# Backplane.net
KiCad netlist of a schematic drawn in Altium Designer
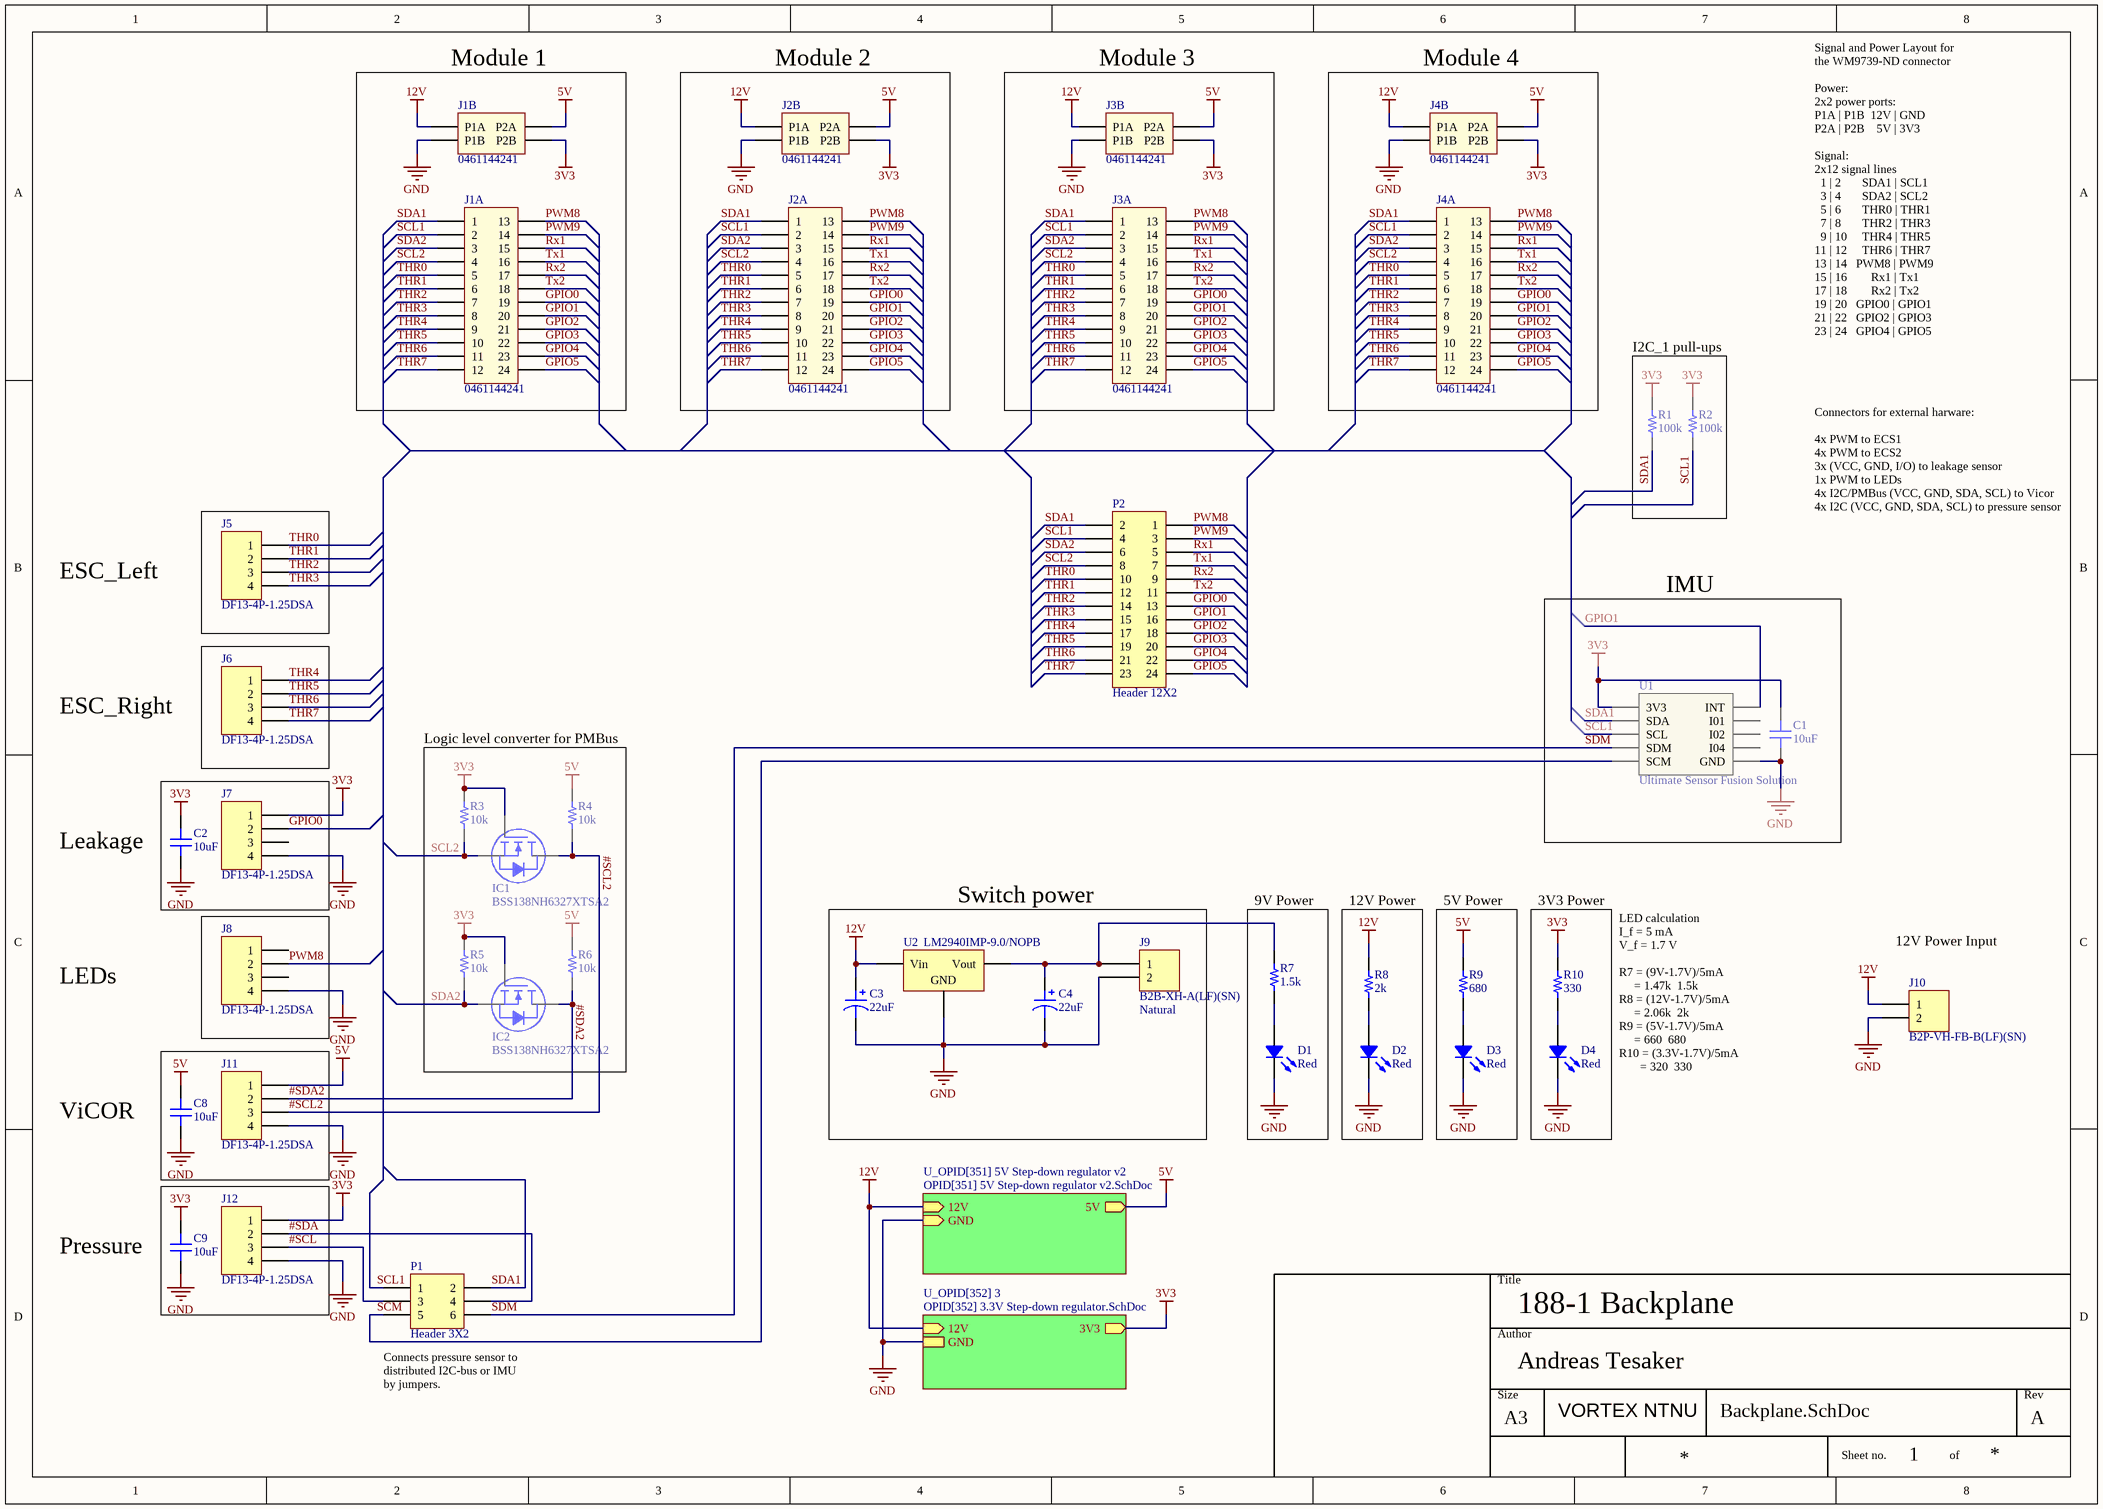
[diagram p0: Backplane.SchDoc]

(export (version "E")
  (design (tool "Eeschema 10.0.6"))
  (components
    (comp (ref "C1")
      (value "10uF")
      (footprint "CAP 1210/3225 - 2.8MM")
      (description "CAP CER 10UF 50V X7S 1210")
      (fields
        (field (name "PART NUMBER") "C3225X7S1H106M250AB")
        (field (name "MANUFACTURER") "TDK Corporation")
      )
      (libsource (lib "Celestial Library Database") (part "Capacitor"))
    )
    (comp (ref "C2")
      (value "10uF")
      (footprint "CAP 1210/3225 - 2.8MM")
      (description "CAP CER 10UF 50V X7S 1210")
      (fields
        (field (name "PART NUMBER") "C3225X7S1H106M250AB")
        (field (name "MANUFACTURER") "TDK Corporation")
      )
      (libsource (lib "Celestial Library Database") (part "Capacitor"))
    )
    (comp (ref "C3")
      (value "22uF")
      (footprint "CAP ALUM 6.6MM")
      (description "CAP ALUM 22UF 20% 35V SMD")
      (fields (field (name "PART NUMBER") "UWJ1V220MCL1GB") (field (name "MANUFACTURER") "Nichicon"))
      (libsource (lib "Celestial Library Database") (part "Polarised Capacitor"))
    )
    (comp (ref "C4")
      (value "22uF")
      (footprint "CAP POL 2917/7343")
      (description "CAP TANT 22UF 20V 20% 2917")
      (fields (field (name "PART NUMBER") "293D226X0020D2TE3") (field (name "MANUFACTURER") "Vishay Sprague"))
      (libsource (lib "Celestial Library Database") (part "Polarised Capacitor"))
    )
    (comp (ref "C8")
      (value "10uF")
      (footprint "CAP 1210/3225 - 2.8MM")
      (description "CAP CER 10UF 50V X7S 1210")
      (fields
        (field (name "PART NUMBER") "C3225X7S1H106M250AB")
        (field (name "MANUFACTURER") "TDK Corporation")
      )
      (libsource (lib "Celestial Library Database") (part "Capacitor"))
    )
    (comp (ref "C9")
      (value "10uF")
      (footprint "CAP 1210/3225 - 2.8MM")
      (description "CAP CER 10UF 50V X7S 1210")
      (fields
        (field (name "PART NUMBER") "C3225X7S1H106M250AB")
        (field (name "MANUFACTURER") "TDK Corporation")
      )
      (libsource (lib "Celestial Library Database") (part "Capacitor"))
    )
    (comp (ref "D1")
      (value "Red")
      (footprint "LED 0805/2012 RED")
      (description "LED RED DIFFUSED 0805 SMD")
      (fields
        (field (name "PART NUMBER") "LH R974-LP-1")
        (field (name "MANUFACTURER") "OSRAM Opto Semiconductors Inc.")
      )
      (libsource (lib "Celestial Library Database") (part "LED"))
    )
    (comp (ref "D2")
      (value "Red")
      (footprint "LED 0805/2012 RED")
      (description "LED RED DIFFUSED 0805 SMD")
      (fields
        (field (name "PART NUMBER") "LH R974-LP-1")
        (field (name "MANUFACTURER") "OSRAM Opto Semiconductors Inc.")
      )
      (libsource (lib "Celestial Library Database") (part "LED"))
    )
    (comp (ref "D3")
      (value "Red")
      (footprint "LED 0805/2012 RED")
      (description "LED RED DIFFUSED 0805 SMD")
      (fields
        (field (name "PART NUMBER") "LH R974-LP-1")
        (field (name "MANUFACTURER") "OSRAM Opto Semiconductors Inc.")
      )
      (libsource (lib "Celestial Library Database") (part "LED"))
    )
    (comp (ref "D4")
      (value "Red")
      (footprint "LED 0805/2012 RED")
      (description "LED RED DIFFUSED 0805 SMD")
      (fields
        (field (name "PART NUMBER") "LH R974-LP-1")
        (field (name "MANUFACTURER") "OSRAM Opto Semiconductors Inc.")
      )
      (libsource (lib "Celestial Library Database") (part "LED"))
    )
    (comp (ref "IC1")
      (value "BSS138NH6327XTSA2")
      (footprint "INFINEON SOT-23-3")
      (description "MOSFET N-CH 60V 230MA SOT-23")
      (fields (field (name "MANUFACTURER") "Infineon Technologies"))
      (libsource (lib "Celestial Library Database") (part "INFINEON MOSFET N-CH SOT-23-3"))
    )
    (comp (ref "IC2")
      (value "BSS138NH6327XTSA2")
      (footprint "INFINEON SOT-23-3")
      (description "MOSFET N-CH 60V 230MA SOT-23")
      (fields (field (name "MANUFACTURER") "Infineon Technologies"))
      (libsource (lib "Celestial Library Database") (part "INFINEON MOSFET N-CH SOT-23-3"))
    )
    (comp (ref "J1")
      (value "0461144241")
      (footprint "LPH_VERT.RECEPT._ASSY_4PX24S")
      (libsource (lib "Vortex-component-database") (part "LPHPower_connector"))
    )
    (comp (ref "J2")
      (value "0461144241")
      (footprint "LPH_VERT.RECEPT._ASSY_4PX24S")
      (libsource (lib "Vortex-component-database") (part "LPHPower_connector"))
    )
    (comp (ref "J3")
      (value "0461144241")
      (footprint "LPH_VERT.RECEPT._ASSY_4PX24S")
      (libsource (lib "Vortex-component-database") (part "LPHPower_connector"))
    )
    (comp (ref "J4")
      (value "0461144241")
      (footprint "LPH_VERT.RECEPT._ASSY_4PX24S")
      (libsource (lib "Vortex-component-database") (part "LPHPower_connector"))
    )
    (comp (ref "J5")
      (value "DF13-4P-1.25DSA")
      (footprint "HDRV4W35P125_1X4_665X340X430P")
      (libsource (lib "Vortex-component-database") (part "Header 4"))
    )
    (comp (ref "J6")
      (value "DF13-4P-1.25DSA")
      (footprint "HDRV4W35P125_1X4_665X340X430P")
      (libsource (lib "Vortex-component-database") (part "Header 4"))
    )
    (comp (ref "J7")
      (value "DF13-4P-1.25DSA")
      (footprint "HDRV4W35P125_1X4_665X340X430P")
      (libsource (lib "Vortex-component-database") (part "Header 4"))
    )
    (comp (ref "J8")
      (value "DF13-4P-1.25DSA")
      (footprint "HDRV4W35P125_1X4_665X340X430P")
      (libsource (lib "Vortex-component-database") (part "Header 4"))
    )
    (comp (ref "J9")
      (value "B2B-XH-A(LF)(SN)")
      (footprint "JST XH B2B-XH-A")
      (description "CONN HEADER XH TOP 2POS 2.5MM")
      (fields (field (name "COLOUR") "Natural") (field (name "MANUFACTURER") "JST Sales America Inc."))
      (libsource (lib "Celestial Library Database") (part "2 Pin"))
    )
    (comp (ref "J10")
      (value "B2P-VH-FB-B(LF)(SN)")
      (footprint "B2P-VH-FB-B")
      (libsource (lib "Vortex-component-database") (part "Header 2"))
    )
    (comp (ref "J11")
      (value "DF13-4P-1.25DSA")
      (footprint "HDRV4W35P125_1X4_665X340X430P")
      (libsource (lib "Vortex-component-database") (part "Header 4"))
    )
    (comp (ref "J12")
      (value "DF13-4P-1.25DSA")
      (footprint "HDRV4W35P125_1X4_665X340X430P")
      (libsource (lib "Vortex-component-database") (part "Header 4"))
    )
    (comp (ref "P1")
      (value "Header 3X2")
      (footprint "HDR2X3")
      (description "Header, 3-Pin, Dual row")
      (fields (field (name "PUBLISHER") "Altium Limited"))
      (libsource (lib "Miscellaneous Connectors") (part "Header 3X2"))
    )
    (comp (ref "P2")
      (value "Header 12X2")
      (footprint "HDR2X12")
      (description "Header, 12-Pin, Dual row")
      (fields (field (name "PUBLISHER") "Altium Limited"))
      (libsource (lib "Miscellaneous Connectors") (part "Header 12X2"))
    )
    (comp (ref "R1")
      (value "100k")
      (footprint "RES 0805/2012")
      (description "RES SMD 100K OHM 1% 1/8W 0805")
      (fields
        (field (name "PART NUMBER") "ERJ-6ENF1003V")
        (field (name "MANUFACTURER") "Panasonic Electronic Components")
      )
      (libsource (lib "Celestial Library Database") (part "Resistor"))
    )
    (comp (ref "R2")
      (value "100k")
      (footprint "RES 0805/2012")
      (description "RES SMD 100K OHM 1% 1/8W 0805")
      (fields
        (field (name "PART NUMBER") "ERJ-6ENF1003V")
        (field (name "MANUFACTURER") "Panasonic Electronic Components")
      )
      (libsource (lib "Celestial Library Database") (part "Resistor"))
    )
    (comp (ref "R3")
      (value "10k")
      (footprint "RES 0805/2012")
      (description "RES SMD 10K OHM 1% 1/8W 0805")
      (fields
        (field (name "PART NUMBER") "ERJ-6ENF1002V")
        (field (name "MANUFACTURER") "Panasonic Electronic Components")
      )
      (libsource (lib "Celestial Library Database") (part "Resistor"))
    )
    (comp (ref "R4")
      (value "10k")
      (footprint "RES 0805/2012")
      (description "RES SMD 10K OHM 1% 1/8W 0805")
      (fields
        (field (name "PART NUMBER") "ERJ-6ENF1002V")
        (field (name "MANUFACTURER") "Panasonic Electronic Components")
      )
      (libsource (lib "Celestial Library Database") (part "Resistor"))
    )
    (comp (ref "R5")
      (value "10k")
      (footprint "RES 0805/2012")
      (description "RES SMD 10K OHM 1% 1/8W 0805")
      (fields
        (field (name "PART NUMBER") "ERJ-6ENF1002V")
        (field (name "MANUFACTURER") "Panasonic Electronic Components")
      )
      (libsource (lib "Celestial Library Database") (part "Resistor"))
    )
    (comp (ref "R6")
      (value "10k")
      (footprint "RES 0805/2012")
      (description "RES SMD 10K OHM 1% 1/8W 0805")
      (fields
        (field (name "PART NUMBER") "ERJ-6ENF1002V")
        (field (name "MANUFACTURER") "Panasonic Electronic Components")
      )
      (libsource (lib "Celestial Library Database") (part "Resistor"))
    )
    (comp (ref "R7")
      (value "1.5k")
      (footprint "RES 0805/2012")
      (description "RES SMD 1.5K OHM 0.1% 1/8W 0805")
      (fields
        (field (name "PART NUMBER") "ERA-6AEB152V")
        (field (name "MANUFACTURER") "Panasonic Electronic Components")
      )
      (libsource (lib "Celestial Library Database") (part "Resistor"))
    )
    (comp (ref "R8")
      (value "2k")
      (footprint "RES 0805/2012")
      (description "RES SMD 2K OHM 0.1% 1/8W 0805")
      (fields
        (field (name "PART NUMBER") "ERA-6AEB202V")
        (field (name "MANUFACTURER") "Panasonic Electronic Components")
      )
      (libsource (lib "Celestial Library Database") (part "Resistor"))
    )
    (comp (ref "R9")
      (value "680")
      (footprint "RES 0805/2012")
      (description "RES SMD 680 OHM 1% 1/8W 0805")
      (fields
        (field (name "PART NUMBER") "ERJ-6ENF6800V")
        (field (name "MANUFACTURER") "Panasonic Electronic Components")
      )
      (libsource (lib "Celestial Library Database") (part "Resistor"))
    )
    (comp (ref "R10")
      (value "330")
      (footprint "RES 0805/2012")
      (description "RES SMD 330 OHM 5% 1/2W 0805")
      (fields
        (field (name "PART NUMBER") "ERJ-P06J331V")
        (field (name "MANUFACTURER") "Panasonic Electronic Components")
      )
      (libsource (lib "Celestial Library Database") (part "Resistor"))
    )
    (comp (ref "U1")
      (value "Ultimate Sensor Fusion Solution")
      (footprint "Ultimate Sensor Fusion Solution")
      (libsource (lib "Vortex-component-database") (part "Ultimate Sensor Fusion Solution"))
    )
    (comp (ref "U2")
      (value "LM2940IMP-9.0/NOPB")
      (footprint "SOT230P700X180-4N")
      (libsource (lib "Vortex-component-database") (part "Volt_Reg"))
    )
  )
  (nets
    (net (code "1") (name "/GPIO0") (class "Default")
      (node (ref "J1") (pin "19") (pinfunction "19_19") (pintype "passive"))
      (node (ref "J2") (pin "19") (pinfunction "19_19") (pintype "passive"))
      (node (ref "J3") (pin "19") (pinfunction "19_19") (pintype "passive"))
      (node (ref "J4") (pin "19") (pinfunction "19_19") (pintype "passive"))
      (node (ref "J7") (pin "2") (pinfunction "2_2") (pintype "passive"))
      (node (ref "P2") (pin "13") (pinfunction "13_13") (pintype "passive"))
    )
    (net (code "2") (name "/GPIO1") (class "Default")
      (node (ref "J1") (pin "20") (pinfunction "20_20") (pintype "passive"))
      (node (ref "J2") (pin "20") (pinfunction "20_20") (pintype "passive"))
      (node (ref "J3") (pin "20") (pinfunction "20_20") (pintype "passive"))
      (node (ref "J4") (pin "20") (pinfunction "20_20") (pintype "passive"))
      (node (ref "P2") (pin "16") (pinfunction "16_16") (pintype "passive"))
      (node (ref "U1") (pin "6") (pinfunction "INT_6") (pintype "passive"))
    )
    (net (code "3") (name "/GPIO2") (class "Default")
      (node (ref "J1") (pin "21") (pinfunction "21_21") (pintype "passive"))
      (node (ref "J2") (pin "21") (pinfunction "21_21") (pintype "passive"))
      (node (ref "J3") (pin "21") (pinfunction "21_21") (pintype "passive"))
      (node (ref "J4") (pin "21") (pinfunction "21_21") (pintype "passive"))
      (node (ref "P2") (pin "18") (pinfunction "18_18") (pintype "passive"))
    )
    (net (code "4") (name "/GPIO3") (class "Default")
      (node (ref "J1") (pin "22") (pinfunction "22_22") (pintype "passive"))
      (node (ref "J2") (pin "22") (pinfunction "22_22") (pintype "passive"))
      (node (ref "J3") (pin "22") (pinfunction "22_22") (pintype "passive"))
      (node (ref "J4") (pin "22") (pinfunction "22_22") (pintype "passive"))
      (node (ref "P2") (pin "20") (pinfunction "20_20") (pintype "passive"))
    )
    (net (code "5") (name "/GPIO4") (class "Default")
      (node (ref "J1") (pin "23") (pinfunction "23_23") (pintype "passive"))
      (node (ref "J2") (pin "23") (pinfunction "23_23") (pintype "passive"))
      (node (ref "J3") (pin "23") (pinfunction "23_23") (pintype "passive"))
      (node (ref "J4") (pin "23") (pinfunction "23_23") (pintype "passive"))
      (node (ref "P2") (pin "22") (pinfunction "22_22") (pintype "passive"))
    )
    (net (code "6") (name "/GPIO5") (class "Default")
      (node (ref "J1") (pin "24") (pinfunction "24_24") (pintype "passive"))
      (node (ref "J2") (pin "24") (pinfunction "24_24") (pintype "passive"))
      (node (ref "J3") (pin "24") (pinfunction "24_24") (pintype "passive"))
      (node (ref "J4") (pin "24") (pinfunction "24_24") (pintype "passive"))
      (node (ref "P2") (pin "24") (pinfunction "24_24") (pintype "passive"))
    )
    (net (code "7") (name "/PWM8") (class "Default")
      (node (ref "J1") (pin "13") (pinfunction "13_13") (pintype "passive"))
      (node (ref "J2") (pin "13") (pinfunction "13_13") (pintype "passive"))
      (node (ref "J3") (pin "13") (pinfunction "13_13") (pintype "passive"))
      (node (ref "J4") (pin "13") (pinfunction "13_13") (pintype "passive"))
      (node (ref "J8") (pin "2") (pinfunction "2_2") (pintype "passive"))
      (node (ref "P2") (pin "1") (pinfunction "1_1") (pintype "passive"))
    )
    (net (code "8") (name "/PWM9") (class "Default")
      (node (ref "J1") (pin "14") (pinfunction "14_14") (pintype "passive"))
      (node (ref "J2") (pin "14") (pinfunction "14_14") (pintype "passive"))
      (node (ref "J3") (pin "14") (pinfunction "14_14") (pintype "passive"))
      (node (ref "J4") (pin "14") (pinfunction "14_14") (pintype "passive"))
      (node (ref "P2") (pin "3") (pinfunction "3_3") (pintype "passive"))
    )
    (net (code "9") (name "/Rx1") (class "Default")
      (node (ref "J1") (pin "15") (pinfunction "15_15") (pintype "passive"))
      (node (ref "J2") (pin "15") (pinfunction "15_15") (pintype "passive"))
      (node (ref "J3") (pin "15") (pinfunction "15_15") (pintype "passive"))
      (node (ref "J4") (pin "15") (pinfunction "15_15") (pintype "passive"))
      (node (ref "P2") (pin "5") (pinfunction "5_5") (pintype "passive"))
    )
    (net (code "10") (name "/Rx2") (class "Default")
      (node (ref "J1") (pin "17") (pinfunction "17_17") (pintype "passive"))
      (node (ref "J2") (pin "17") (pinfunction "17_17") (pintype "passive"))
      (node (ref "J3") (pin "17") (pinfunction "17_17") (pintype "passive"))
      (node (ref "J4") (pin "17") (pinfunction "17_17") (pintype "passive"))
      (node (ref "P2") (pin "9") (pinfunction "9_9") (pintype "passive"))
    )
    (net (code "11") (name "/SCL1") (class "Default")
      (node (ref "J1") (pin "2") (pinfunction "2_2") (pintype "passive"))
      (node (ref "J2") (pin "2") (pinfunction "2_2") (pintype "passive"))
      (node (ref "J3") (pin "2") (pinfunction "2_2") (pintype "passive"))
      (node (ref "J4") (pin "2") (pinfunction "2_2") (pintype "passive"))
      (node (ref "P1") (pin "1") (pinfunction "1_1") (pintype "passive"))
      (node (ref "P2") (pin "4") (pinfunction "4_4") (pintype "passive"))
      (node (ref "R2") (pin "1") (pinfunction "1_1") (pintype "passive"))
      (node (ref "U1") (pin "4") (pinfunction "SCL_4") (pintype "passive"))
    )
    (net (code "12") (name "/SCL2") (class "Default")
      (node (ref "IC1") (pin "3") (pinfunction "S_3") (pintype "passive"))
      (node (ref "J1") (pin "4") (pinfunction "4_4") (pintype "passive"))
      (node (ref "J2") (pin "4") (pinfunction "4_4") (pintype "passive"))
      (node (ref "J3") (pin "4") (pinfunction "4_4") (pintype "passive"))
      (node (ref "J4") (pin "4") (pinfunction "4_4") (pintype "passive"))
      (node (ref "P2") (pin "8") (pinfunction "8_8") (pintype "passive"))
      (node (ref "R3") (pin "2") (pinfunction "2_2") (pintype "passive"))
    )
    (net (code "13") (name "/SDA1") (class "Default")
      (node (ref "J1") (pin "1") (pinfunction "1_1") (pintype "passive"))
      (node (ref "J2") (pin "1") (pinfunction "1_1") (pintype "passive"))
      (node (ref "J3") (pin "1") (pinfunction "1_1") (pintype "passive"))
      (node (ref "J4") (pin "1") (pinfunction "1_1") (pintype "passive"))
      (node (ref "P1") (pin "2") (pinfunction "2_2") (pintype "passive"))
      (node (ref "P2") (pin "2") (pinfunction "2_2") (pintype "passive"))
      (node (ref "R1") (pin "1") (pinfunction "1_1") (pintype "passive"))
      (node (ref "U1") (pin "5") (pinfunction "SDA_5") (pintype "passive"))
    )
    (net (code "14") (name "/SDA2") (class "Default")
      (node (ref "IC2") (pin "3") (pinfunction "S_3") (pintype "passive"))
      (node (ref "J1") (pin "3") (pinfunction "3_3") (pintype "passive"))
      (node (ref "J2") (pin "3") (pinfunction "3_3") (pintype "passive"))
      (node (ref "J3") (pin "3") (pinfunction "3_3") (pintype "passive"))
      (node (ref "J4") (pin "3") (pinfunction "3_3") (pintype "passive"))
      (node (ref "P2") (pin "6") (pinfunction "6_6") (pintype "passive"))
      (node (ref "R5") (pin "2") (pinfunction "2_2") (pintype "passive"))
    )
    (net (code "15") (name "/THR0") (class "Default")
      (node (ref "J1") (pin "5") (pinfunction "5_5") (pintype "passive"))
      (node (ref "J2") (pin "5") (pinfunction "5_5") (pintype "passive"))
      (node (ref "J3") (pin "5") (pinfunction "5_5") (pintype "passive"))
      (node (ref "J4") (pin "5") (pinfunction "5_5") (pintype "passive"))
      (node (ref "J5") (pin "1") (pinfunction "1_1") (pintype "passive"))
      (node (ref "P2") (pin "10") (pinfunction "10_10") (pintype "passive"))
    )
    (net (code "16") (name "/THR1") (class "Default")
      (node (ref "J1") (pin "6") (pinfunction "6_6") (pintype "passive"))
      (node (ref "J2") (pin "6") (pinfunction "6_6") (pintype "passive"))
      (node (ref "J3") (pin "6") (pinfunction "6_6") (pintype "passive"))
      (node (ref "J4") (pin "6") (pinfunction "6_6") (pintype "passive"))
      (node (ref "J5") (pin "2") (pinfunction "2_2") (pintype "passive"))
      (node (ref "P2") (pin "12") (pinfunction "12_12") (pintype "passive"))
    )
    (net (code "17") (name "/THR2") (class "Default")
      (node (ref "J1") (pin "7") (pinfunction "7_7") (pintype "passive"))
      (node (ref "J2") (pin "7") (pinfunction "7_7") (pintype "passive"))
      (node (ref "J3") (pin "7") (pinfunction "7_7") (pintype "passive"))
      (node (ref "J4") (pin "7") (pinfunction "7_7") (pintype "passive"))
      (node (ref "J5") (pin "3") (pinfunction "3_3") (pintype "passive"))
      (node (ref "P2") (pin "14") (pinfunction "14_14") (pintype "passive"))
    )
    (net (code "18") (name "/THR3") (class "Default")
      (node (ref "J1") (pin "8") (pinfunction "8_8") (pintype "passive"))
      (node (ref "J2") (pin "8") (pinfunction "8_8") (pintype "passive"))
      (node (ref "J3") (pin "8") (pinfunction "8_8") (pintype "passive"))
      (node (ref "J4") (pin "8") (pinfunction "8_8") (pintype "passive"))
      (node (ref "J5") (pin "4") (pinfunction "4_4") (pintype "passive"))
      (node (ref "P2") (pin "15") (pinfunction "15_15") (pintype "passive"))
    )
    (net (code "19") (name "/THR4") (class "Default")
      (node (ref "J1") (pin "9") (pinfunction "9_9") (pintype "passive"))
      (node (ref "J2") (pin "9") (pinfunction "9_9") (pintype "passive"))
      (node (ref "J3") (pin "9") (pinfunction "9_9") (pintype "passive"))
      (node (ref "J4") (pin "9") (pinfunction "9_9") (pintype "passive"))
      (node (ref "J6") (pin "1") (pinfunction "1_1") (pintype "passive"))
      (node (ref "P2") (pin "17") (pinfunction "17_17") (pintype "passive"))
    )
    (net (code "20") (name "/THR5") (class "Default")
      (node (ref "J1") (pin "10") (pinfunction "10_10") (pintype "passive"))
      (node (ref "J2") (pin "10") (pinfunction "10_10") (pintype "passive"))
      (node (ref "J3") (pin "10") (pinfunction "10_10") (pintype "passive"))
      (node (ref "J4") (pin "10") (pinfunction "10_10") (pintype "passive"))
      (node (ref "J6") (pin "2") (pinfunction "2_2") (pintype "passive"))
      (node (ref "P2") (pin "19") (pinfunction "19_19") (pintype "passive"))
    )
    (net (code "21") (name "/THR6") (class "Default")
      (node (ref "J1") (pin "11") (pinfunction "11_11") (pintype "passive"))
      (node (ref "J2") (pin "11") (pinfunction "11_11") (pintype "passive"))
      (node (ref "J3") (pin "11") (pinfunction "11_11") (pintype "passive"))
      (node (ref "J4") (pin "11") (pinfunction "11_11") (pintype "passive"))
      (node (ref "J6") (pin "3") (pinfunction "3_3") (pintype "passive"))
      (node (ref "P2") (pin "21") (pinfunction "21_21") (pintype "passive"))
    )
    (net (code "22") (name "/THR7") (class "Default")
      (node (ref "J1") (pin "12") (pinfunction "12_12") (pintype "passive"))
      (node (ref "J2") (pin "12") (pinfunction "12_12") (pintype "passive"))
      (node (ref "J3") (pin "12") (pinfunction "12_12") (pintype "passive"))
      (node (ref "J4") (pin "12") (pinfunction "12_12") (pintype "passive"))
      (node (ref "J6") (pin "4") (pinfunction "4_4") (pintype "passive"))
      (node (ref "P2") (pin "23") (pinfunction "23_23") (pintype "passive"))
    )
    (net (code "23") (name "/Tx1") (class "Default")
      (node (ref "J1") (pin "16") (pinfunction "16_16") (pintype "passive"))
      (node (ref "J2") (pin "16") (pinfunction "16_16") (pintype "passive"))
      (node (ref "J3") (pin "16") (pinfunction "16_16") (pintype "passive"))
      (node (ref "J4") (pin "16") (pinfunction "16_16") (pintype "passive"))
      (node (ref "P2") (pin "7") (pinfunction "7_7") (pintype "passive"))
    )
    (net (code "24") (name "/Tx2") (class "Default")
      (node (ref "J1") (pin "18") (pinfunction "18_18") (pintype "passive"))
      (node (ref "J2") (pin "18") (pinfunction "18_18") (pintype "passive"))
      (node (ref "J3") (pin "18") (pinfunction "18_18") (pintype "passive"))
      (node (ref "J4") (pin "18") (pinfunction "18_18") (pintype "passive"))
      (node (ref "P2") (pin "11") (pinfunction "11_11") (pintype "passive"))
    )
    (net (code "25") (name "3V3") (class "Default")
      (node (ref "C1") (pin "2") (pinfunction "2_2") (pintype "passive"))
      (node (ref "C2") (pin "2") (pinfunction "2_2") (pintype "passive"))
      (node (ref "C9") (pin "2") (pinfunction "2_2") (pintype "passive"))
      (node (ref "IC1") (pin "1") (pinfunction "G_1") (pintype "passive"))
      (node (ref "IC2") (pin "1") (pinfunction "G_1") (pintype "passive"))
      (node (ref "J1") (pin "P2B") (pinfunction "P2B_P2B") (pintype "passive"))
      (node (ref "J12") (pin "1") (pinfunction "1_1") (pintype "passive"))
      (node (ref "J2") (pin "P2B") (pinfunction "P2B_P2B") (pintype "passive"))
      (node (ref "J3") (pin "P2B") (pinfunction "P2B_P2B") (pintype "passive"))
      (node (ref "J4") (pin "P2B") (pinfunction "P2B_P2B") (pintype "passive"))
      (node (ref "J7") (pin "1") (pinfunction "1_1") (pintype "passive"))
      (node (ref "R1") (pin "2") (pinfunction "2_2") (pintype "passive"))
      (node (ref "R10") (pin "2") (pinfunction "2_2") (pintype "passive"))
      (node (ref "R2") (pin "2") (pinfunction "2_2") (pintype "passive"))
      (node (ref "R3") (pin "1") (pinfunction "1_1") (pintype "passive"))
      (node (ref "R5") (pin "1") (pinfunction "1_1") (pintype "passive"))
      (node (ref "U1") (pin "2") (pinfunction "3V3_2") (pintype "passive"))
    )
    (net (code "26") (name "5V") (class "Default")
      (node (ref "C8") (pin "2") (pinfunction "2_2") (pintype "passive"))
      (node (ref "J1") (pin "P2A") (pinfunction "P2A_P2A") (pintype "passive"))
      (node (ref "J11") (pin "1") (pinfunction "1_1") (pintype "passive"))
      (node (ref "J2") (pin "P2A") (pinfunction "P2A_P2A") (pintype "passive"))
      (node (ref "J3") (pin "P2A") (pinfunction "P2A_P2A") (pintype "passive"))
      (node (ref "J4") (pin "P2A") (pinfunction "P2A_P2A") (pintype "passive"))
      (node (ref "R4") (pin "1") (pinfunction "1_1") (pintype "passive"))
      (node (ref "R6") (pin "1") (pinfunction "1_1") (pintype "passive"))
      (node (ref "R9") (pin "2") (pinfunction "2_2") (pintype "passive"))
    )
    (net (code "27") (name "12V") (class "Default")
      (node (ref "C3") (pin "1") (pinfunction "1_1") (pintype "passive"))
      (node (ref "J1") (pin "P1A") (pinfunction "P1A_P1A") (pintype "passive"))
      (node (ref "J10") (pin "1") (pinfunction "1_1") (pintype "passive"))
      (node (ref "J2") (pin "P1A") (pinfunction "P1A_P1A") (pintype "passive"))
      (node (ref "J3") (pin "P1A") (pinfunction "P1A_P1A") (pintype "passive"))
      (node (ref "J4") (pin "P1A") (pinfunction "P1A_P1A") (pintype "passive"))
      (node (ref "R8") (pin "2") (pinfunction "2_2") (pintype "passive"))
      (node (ref "U2") (pin "1") (pinfunction "Vin_1") (pintype "passive"))
    )
    (net (code "28") (name "GND") (class "Default")
      (node (ref "C1") (pin "1") (pinfunction "1_1") (pintype "passive"))
      (node (ref "C2") (pin "1") (pinfunction "1_1") (pintype "passive"))
      (node (ref "C3") (pin "2") (pinfunction "2_2") (pintype "passive"))
      (node (ref "C4") (pin "2") (pinfunction "2_2") (pintype "passive"))
      (node (ref "C8") (pin "1") (pinfunction "1_1") (pintype "passive"))
      (node (ref "C9") (pin "1") (pinfunction "1_1") (pintype "passive"))
      (node (ref "D1") (pin "2") (pinfunction "2_2") (pintype "passive"))
      (node (ref "D2") (pin "2") (pinfunction "2_2") (pintype "passive"))
      (node (ref "D3") (pin "2") (pinfunction "2_2") (pintype "passive"))
      (node (ref "D4") (pin "2") (pinfunction "2_2") (pintype "passive"))
      (node (ref "J1") (pin "P1B") (pinfunction "P1B_P1B") (pintype "passive"))
      (node (ref "J10") (pin "2") (pinfunction "2_2") (pintype "passive"))
      (node (ref "J11") (pin "4") (pinfunction "4_4") (pintype "passive"))
      (node (ref "J12") (pin "4") (pinfunction "4_4") (pintype "passive"))
      (node (ref "J2") (pin "P1B") (pinfunction "P1B_P1B") (pintype "passive"))
      (node (ref "J3") (pin "P1B") (pinfunction "P1B_P1B") (pintype "passive"))
      (node (ref "J4") (pin "P1B") (pinfunction "P1B_P1B") (pintype "passive"))
      (node (ref "J7") (pin "4") (pinfunction "4_4") (pintype "passive"))
      (node (ref "J8") (pin "4") (pinfunction "4_4") (pintype "passive"))
      (node (ref "J9") (pin "2") (pinfunction "2_2") (pintype "passive"))
      (node (ref "U1") (pin "1") (pinfunction "GND_1") (pintype "passive"))
      (node (ref "U2") (pin "2") (pinfunction "GND_2") (pintype "passive"))
    )
    (net (code "29") (name "Net-(D1-Pad1)") (class "Default")
      (node (ref "D1") (pin "1") (pinfunction "1_1") (pintype "passive"))
      (node (ref "R7") (pin "1") (pinfunction "1_1") (pintype "passive"))
    )
    (net (code "30") (name "Net-(D2-Pad1)") (class "Default")
      (node (ref "D2") (pin "1") (pinfunction "1_1") (pintype "passive"))
      (node (ref "R8") (pin "1") (pinfunction "1_1") (pintype "passive"))
    )
    (net (code "31") (name "Net-(D3-Pad1)") (class "Default")
      (node (ref "D3") (pin "1") (pinfunction "1_1") (pintype "passive"))
      (node (ref "R9") (pin "1") (pinfunction "1_1") (pintype "passive"))
    )
    (net (code "32") (name "Net-(D4-Pad1)") (class "Default")
      (node (ref "D4") (pin "1") (pinfunction "1_1") (pintype "passive"))
      (node (ref "R10") (pin "1") (pinfunction "1_1") (pintype "passive"))
    )
    (net (code "33") (name "Net-(IC1-D)") (class "Default")
      (node (ref "IC1") (pin "2") (pinfunction "D_2") (pintype "passive"))
      (node (ref "J11") (pin "3") (pinfunction "3_3") (pintype "passive"))
      (node (ref "R4") (pin "2") (pinfunction "2_2") (pintype "passive"))
    )
    (net (code "34") (name "Net-(IC2-D)") (class "Default")
      (node (ref "IC2") (pin "2") (pinfunction "D_2") (pintype "passive"))
      (node (ref "J11") (pin "2") (pinfunction "2_2") (pintype "passive"))
      (node (ref "R6") (pin "2") (pinfunction "2_2") (pintype "passive"))
    )
    (net (code "35") (name "Net-(J12-Pad2)") (class "Default")
      (node (ref "J12") (pin "2") (pinfunction "2_2") (pintype "passive"))
      (node (ref "P1") (pin "4") (pinfunction "4_4") (pintype "passive"))
    )
    (net (code "36") (name "Net-(J12-Pad3)") (class "Default")
      (node (ref "J12") (pin "3") (pinfunction "3_3") (pintype "passive"))
      (node (ref "P1") (pin "3") (pinfunction "3_3") (pintype "passive"))
    )
    (net (code "37") (name "Net-(U1-SCM)") (class "Default")
      (node (ref "P1") (pin "5") (pinfunction "5_5") (pintype "passive"))
      (node (ref "U1") (pin "9") (pinfunction "SCM_9") (pintype "passive"))
    )
    (net (code "38") (name "Net-(U1-SDM)") (class "Default")
      (node (ref "P1") (pin "6") (pinfunction "6_6") (pintype "passive"))
      (node (ref "U1") (pin "10") (pinfunction "SDM_10") (pintype "passive"))
    )
    (net (code "39") (name "Net-(U2-Vout)") (class "Default")
      (node (ref "C4") (pin "1") (pinfunction "1_1") (pintype "passive"))
      (node (ref "J9") (pin "1") (pinfunction "1_1") (pintype "passive"))
      (node (ref "R7") (pin "2") (pinfunction "2_2") (pintype "passive"))
      (node (ref "U2") (pin "3") (pinfunction "Vout_3") (pintype "passive"))
    )
    (net (code "40") (name "unconnected-(J7-Pad3)") (class "Default")
      (node (ref "J7") (pin "3") (pinfunction "3_3") (pintype "passive"))
    )
    (net (code "41") (name "unconnected-(J8-Pad1)") (class "Default")
      (node (ref "J8") (pin "1") (pinfunction "1_1") (pintype "passive"))
    )
    (net (code "42") (name "unconnected-(J8-Pad3)") (class "Default")
      (node (ref "J8") (pin "3") (pinfunction "3_3") (pintype "passive"))
    )
    (net (code "43") (name "unconnected-(U1-I01-Pad8)") (class "Default")
      (node (ref "U1") (pin "8") (pinfunction "I01_8") (pintype "passive"))
    )
    (net (code "44") (name "unconnected-(U1-I02-Pad3)") (class "Default")
      (node (ref "U1") (pin "3") (pinfunction "I02_3") (pintype "passive"))
    )
    (net (code "45") (name "unconnected-(U1-I04-Pad7)") (class "Default")
      (node (ref "U1") (pin "7") (pinfunction "I04_7") (pintype "passive"))
    )
  )
)
